# low_power_rfnode.net
KiCad netlist of a schematic drawn in EAGLE
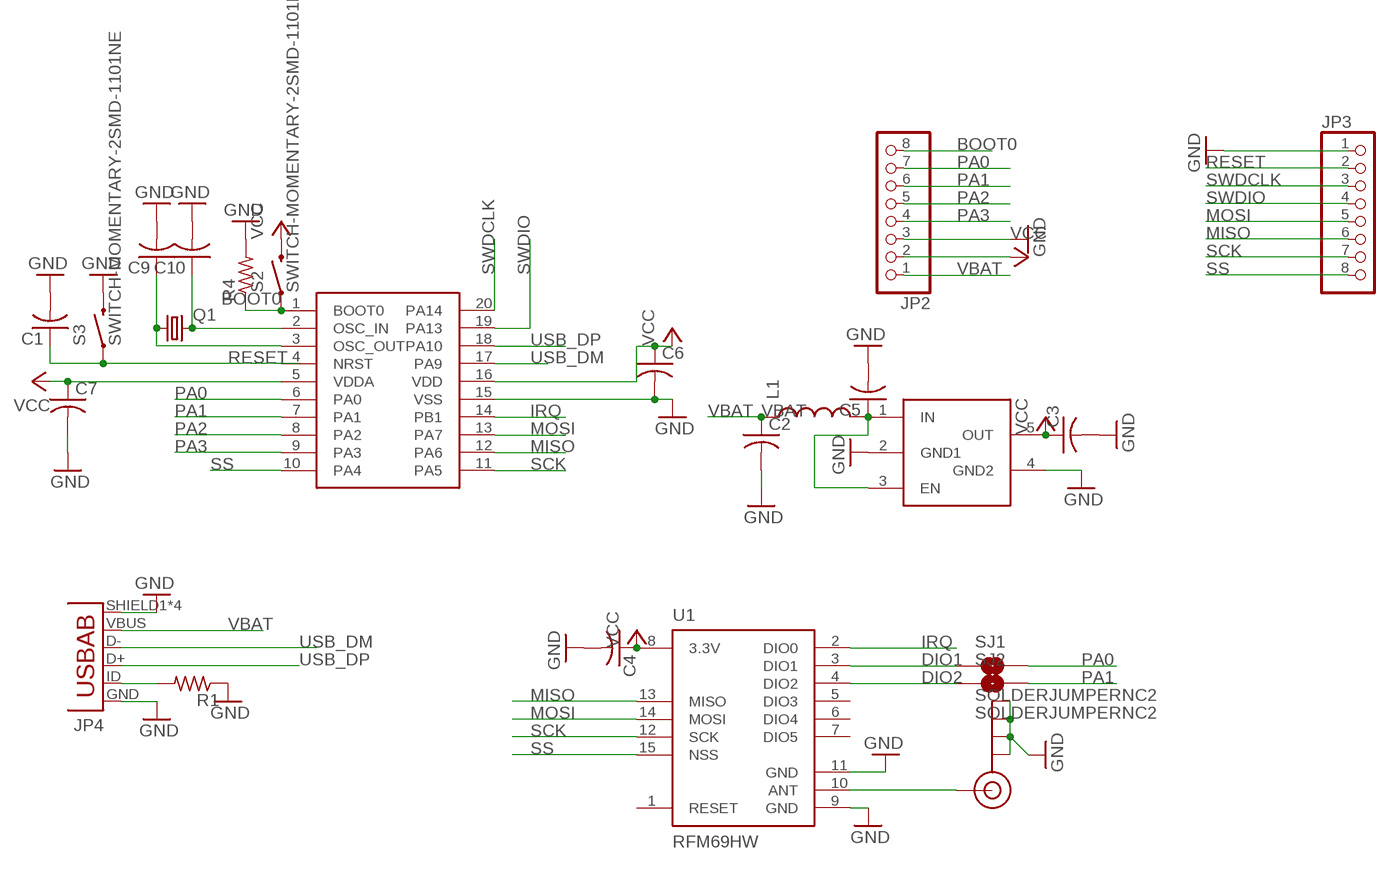
[diagram p0: schematic, sheet 1]

(export (version "E")
  (design (tool "Eeschema 10.0.6"))
  (components
    (comp (ref "C1")
      (value "C-USC0805K")
      (footprint "eagle-import:C0805K")
      (libsource (lib "eagle-import") (part "C-USC0805K"))
    )
    (comp (ref "C2")
      (value "C-USC0805K")
      (footprint "eagle-import:C0805K")
      (libsource (lib "eagle-import") (part "C-USC0805K"))
    )
    (comp (ref "C3")
      (value "C-USC0805K")
      (footprint "eagle-import:C0805K")
      (libsource (lib "eagle-import") (part "C-USC0805K"))
    )
    (comp (ref "C4")
      (value "C-USC0805K")
      (footprint "eagle-import:C0805K")
      (libsource (lib "eagle-import") (part "C-USC0805K"))
    )
    (comp (ref "C5")
      (value "C-USC0805K")
      (footprint "eagle-import:C0805K")
      (libsource (lib "eagle-import") (part "C-USC0805K"))
    )
    (comp (ref "C6")
      (value "C-USC0805K")
      (footprint "eagle-import:C0805K")
      (libsource (lib "eagle-import") (part "C-USC0805K"))
    )
    (comp (ref "C7")
      (value "C-USC0805K")
      (footprint "eagle-import:C0805K")
      (libsource (lib "eagle-import") (part "C-USC0805K"))
    )
    (comp (ref "C9")
      (value "C-USC0805K")
      (footprint "eagle-import:C0805K")
      (libsource (lib "eagle-import") (part "C-USC0805K"))
    )
    (comp (ref "C10")
      (value "C-USC0805K")
      (footprint "eagle-import:C0805K")
      (libsource (lib "eagle-import") (part "C-USC0805K"))
    )
    (comp (ref "J1")
      (value "SMA_EDGE")
      (footprint "eagle-import:SMA-EDGE")
      (libsource (lib "eagle-import") (part "SMA_EDGE"))
    )
    (comp (ref "JP2")
      (value "PINHD-1X8BIG")
      (footprint "eagle-import:1X08-BIG")
      (libsource (lib "eagle-import") (part "PINHD-1X8BIG"))
    )
    (comp (ref "JP3")
      (value "PINHD-1X8BIG")
      (footprint "eagle-import:1X08-BIG")
      (libsource (lib "eagle-import") (part "PINHD-1X8BIG"))
    )
    (comp (ref "JP4")
      (value "USB-AB")
      (footprint "eagle-import:USB-AB-MICRO-SMD")
      (libsource (lib "eagle-import") (part "USB-AB"))
    )
    (comp (ref "L1")
      (value "INDUCTOR0805")
      (footprint "eagle-import:0805")
      (libsource (lib "eagle-import") (part "INDUCTOR0805"))
    )
    (comp (ref "Q1")
      (value "CRYSTALHC49S")
      (footprint "eagle-import:HC49_S")
      (libsource (lib "eagle-import") (part "CRYSTALHC49S"))
    )
    (comp (ref "R1")
      (value "R-US_R0805")
      (footprint "eagle-import:R0805")
      (libsource (lib "eagle-import") (part "R-US_R0805"))
    )
    (comp (ref "R4")
      (value "R-US_R0805")
      (footprint "eagle-import:R0805")
      (libsource (lib "eagle-import") (part "R-US_R0805"))
    )
    (comp (ref "REG")
      (value "TPS783")
      (footprint "eagle-import:SOT23-5")
      (libsource (lib "eagle-import") (part "TPS783"))
    )
    (comp (ref "S2")
      (value "SWITCH-MOMENTARY-2SMD-1101NE")
      (footprint "eagle-import:TACTILE-SWITCH-1101NE")
      (libsource (lib "eagle-import") (part "SWITCH-MOMENTARY-2SMD-1101NE"))
    )
    (comp (ref "S3")
      (value "SWITCH-MOMENTARY-2SMD-1101NE")
      (footprint "eagle-import:TACTILE-SWITCH-1101NE")
      (libsource (lib "eagle-import") (part "SWITCH-MOMENTARY-2SMD-1101NE"))
    )
    (comp (ref "SJ1")
      (value "SOLDERJUMPERNC2")
      (footprint "eagle-import:SJ_2S-NOTRACE")
      (libsource (lib "eagle-import") (part "SOLDERJUMPERNC2"))
    )
    (comp (ref "SJ2")
      (value "SOLDERJUMPERNC2")
      (footprint "eagle-import:SJ_2S-NOTRACE")
      (libsource (lib "eagle-import") (part "SOLDERJUMPERNC2"))
    )
    (comp (ref "U$1")
      (value "STM32F0")
      (footprint "eagle-import:TSSOP20")
      (libsource (lib "eagle-import") (part "STM32F0"))
    )
    (comp (ref "U1")
      (value "RFM69HW")
      (footprint "eagle-import:RFM69W-XXXS2")
      (libsource (lib "eagle-import") (part "RFM69HW"))
    )
  )
  (nets
    (net (code "1") (name "/BOOT0") (class "Default")
      (node (ref "JP2") (pin "8") (pinfunction "8_8") (pintype "passive"))
      (node (ref "R4") (pin "1") (pinfunction "1_1") (pintype "passive"))
      (node (ref "S2") (pin "1") (pinfunction "1_1") (pintype "passive"))
      (node (ref "U$1") (pin "1") (pinfunction "BOOT0_1") (pintype "bidirectional"))
    )
    (net (code "2") (name "/DIO1") (class "Default")
      (node (ref "SJ1") (pin "1") (pinfunction "1_1") (pintype "passive"))
      (node (ref "U1") (pin "3") (pinfunction "DIO1_3") (pintype "bidirectional"))
    )
    (net (code "3") (name "/DIO2") (class "Default")
      (node (ref "SJ2") (pin "1") (pinfunction "1_1") (pintype "passive"))
      (node (ref "U1") (pin "4") (pinfunction "DIO2_4") (pintype "bidirectional"))
    )
    (net (code "4") (name "/IRQ") (class "Default")
      (node (ref "U$1") (pin "14") (pinfunction "PB1_14") (pintype "bidirectional"))
      (node (ref "U1") (pin "2") (pinfunction "DIO0_2") (pintype "bidirectional"))
    )
    (net (code "5") (name "/MISO") (class "Default")
      (node (ref "JP3") (pin "6") (pinfunction "6_6") (pintype "passive"))
      (node (ref "U$1") (pin "12") (pinfunction "PA6_12") (pintype "bidirectional"))
      (node (ref "U1") (pin "13") (pinfunction "MISO_13") (pintype "bidirectional"))
    )
    (net (code "6") (name "/MOSI") (class "Default")
      (node (ref "JP3") (pin "5") (pinfunction "5_5") (pintype "passive"))
      (node (ref "U$1") (pin "13") (pinfunction "PA7_13") (pintype "bidirectional"))
      (node (ref "U1") (pin "14") (pinfunction "MOSI_14") (pintype "input"))
    )
    (net (code "7") (name "/PA0") (class "Default")
      (node (ref "JP2") (pin "7") (pinfunction "7_7") (pintype "passive"))
      (node (ref "SJ1") (pin "2") (pinfunction "2_2") (pintype "passive"))
      (node (ref "U$1") (pin "6") (pinfunction "PA0_6") (pintype "bidirectional"))
    )
    (net (code "8") (name "/PA1") (class "Default")
      (node (ref "JP2") (pin "6") (pinfunction "6_6") (pintype "passive"))
      (node (ref "SJ2") (pin "2") (pinfunction "2_2") (pintype "passive"))
      (node (ref "U$1") (pin "7") (pinfunction "PA1_7") (pintype "bidirectional"))
    )
    (net (code "9") (name "/PA2") (class "Default")
      (node (ref "JP2") (pin "5") (pinfunction "5_5") (pintype "passive"))
      (node (ref "U$1") (pin "8") (pinfunction "PA2_8") (pintype "bidirectional"))
    )
    (net (code "10") (name "/PA3") (class "Default")
      (node (ref "JP2") (pin "4") (pinfunction "4_4") (pintype "passive"))
      (node (ref "U$1") (pin "9") (pinfunction "PA3_9") (pintype "bidirectional"))
    )
    (net (code "11") (name "/RESET") (class "Default")
      (node (ref "C1") (pin "1") (pinfunction "1_1") (pintype "passive"))
      (node (ref "JP3") (pin "2") (pinfunction "2_2") (pintype "passive"))
      (node (ref "S3") (pin "1") (pinfunction "1_1") (pintype "passive"))
      (node (ref "U$1") (pin "4") (pinfunction "NRST_4") (pintype "bidirectional"))
    )
    (net (code "12") (name "/SCK") (class "Default")
      (node (ref "JP3") (pin "7") (pinfunction "7_7") (pintype "passive"))
      (node (ref "U$1") (pin "11") (pinfunction "PA5_11") (pintype "bidirectional"))
      (node (ref "U1") (pin "12") (pinfunction "SCK_12") (pintype "input"))
    )
    (net (code "13") (name "/SS") (class "Default")
      (node (ref "JP3") (pin "8") (pinfunction "8_8") (pintype "passive"))
      (node (ref "U$1") (pin "10") (pinfunction "PA4_10") (pintype "bidirectional"))
      (node (ref "U1") (pin "15") (pinfunction "NSS_15") (pintype "input"))
    )
    (net (code "14") (name "/SWDCLK") (class "Default")
      (node (ref "JP3") (pin "3") (pinfunction "3_3") (pintype "passive"))
      (node (ref "U$1") (pin "20") (pinfunction "PA14_20") (pintype "bidirectional"))
    )
    (net (code "15") (name "/SWDIO") (class "Default")
      (node (ref "JP3") (pin "4") (pinfunction "4_4") (pintype "passive"))
      (node (ref "U$1") (pin "19") (pinfunction "PA13_19") (pintype "bidirectional"))
    )
    (net (code "16") (name "/USB_DM") (class "Default")
      (node (ref "JP4") (pin "D-") (pinfunction "D-_D-") (pintype "bidirectional"))
      (node (ref "U$1") (pin "17") (pinfunction "PA9_17") (pintype "bidirectional"))
    )
    (net (code "17") (name "/USB_DP") (class "Default")
      (node (ref "JP4") (pin "D+") (pinfunction "D+_D+") (pintype "bidirectional"))
      (node (ref "U$1") (pin "18") (pinfunction "PA10_18") (pintype "bidirectional"))
    )
    (net (code "18") (name "/VBAT") (class "Default")
      (node (ref "C2") (pin "1") (pinfunction "1_1") (pintype "passive"))
      (node (ref "JP2") (pin "1") (pinfunction "1_1") (pintype "passive"))
      (node (ref "JP4") (pin "VBUS") (pinfunction "VBUS_VBUS") (pintype "bidirectional"))
      (node (ref "L1") (pin "1") (pinfunction "1_1") (pintype "passive"))
    )
    (net (code "19") (name "GND") (class "Default")
      (node (ref "C1") (pin "2") (pinfunction "2_2") (pintype "passive"))
      (node (ref "C10") (pin "2") (pinfunction "2_2") (pintype "passive"))
      (node (ref "C2") (pin "2") (pinfunction "2_2") (pintype "passive"))
      (node (ref "C3") (pin "2") (pinfunction "2_2") (pintype "passive"))
      (node (ref "C4") (pin "2") (pinfunction "2_2") (pintype "passive"))
      (node (ref "C5") (pin "2") (pinfunction "2_2") (pintype "passive"))
      (node (ref "C6") (pin "2") (pinfunction "2_2") (pintype "passive"))
      (node (ref "C7") (pin "2") (pinfunction "2_2") (pintype "passive"))
      (node (ref "C9") (pin "2") (pinfunction "2_2") (pintype "passive"))
      (node (ref "J1") (pin "GND@0") (pinfunction "GND_GND@0") (pintype "bidirectional"))
      (node (ref "J1") (pin "GND@1") (pinfunction "GND_GND@1") (pintype "bidirectional"))
      (node (ref "J1") (pin "GND@2") (pinfunction "GND_GND@2") (pintype "bidirectional"))
      (node (ref "J1") (pin "GND@3") (pinfunction "GND_GND@3") (pintype "bidirectional"))
      (node (ref "JP2") (pin "3") (pinfunction "3_3") (pintype "passive"))
      (node (ref "JP3") (pin "1") (pinfunction "1_1") (pintype "passive"))
      (node (ref "JP4") (pin "GND") (pinfunction "GND_GND") (pintype "bidirectional"))
      (node (ref "JP4") (pin "SHIELD1") (pinfunction "SHIELD_SHIELD1") (pintype "bidirectional"))
      (node (ref "JP4") (pin "SHIELD2") (pinfunction "SHIELD_SHIELD2") (pintype "bidirectional"))
      (node (ref "JP4") (pin "SHIELD3") (pinfunction "SHIELD_SHIELD3") (pintype "bidirectional"))
      (node (ref "JP4") (pin "SHIELD4") (pinfunction "SHIELD_SHIELD4") (pintype "bidirectional"))
      (node (ref "R1") (pin "1") (pinfunction "1_1") (pintype "passive"))
      (node (ref "R4") (pin "2") (pinfunction "2_2") (pintype "passive"))
      (node (ref "REG") (pin "2") (pinfunction "GND1_2") (pintype "power_in"))
      (node (ref "REG") (pin "4") (pinfunction "GND2_4") (pintype "power_in"))
      (node (ref "S3") (pin "2") (pinfunction "2_2") (pintype "passive"))
      (node (ref "U$1") (pin "15") (pinfunction "VSS_15") (pintype "bidirectional"))
      (node (ref "U1") (pin "11") (pinfunction "GND_11") (pintype "power_in"))
      (node (ref "U1") (pin "9") (pinfunction "GND_9") (pintype "power_in"))
    )
    (net (code "20") (name "Net-(J1-SIGNAL)") (class "Default")
      (node (ref "J1") (pin "SIG") (pinfunction "SIGNAL_SIG") (pintype "bidirectional"))
      (node (ref "U1") (pin "10") (pinfunction "ANT_10") (pintype "passive"))
    )
    (net (code "21") (name "Net-(JP4-USBID)") (class "Default")
      (node (ref "JP4") (pin "ID") (pinfunction "USBID_ID") (pintype "bidirectional"))
      (node (ref "R1") (pin "2") (pinfunction "2_2") (pintype "passive"))
    )
    (net (code "22") (name "Net-(REG-EN)") (class "Default")
      (node (ref "C5") (pin "1") (pinfunction "1_1") (pintype "passive"))
      (node (ref "L1") (pin "2") (pinfunction "2_2") (pintype "passive"))
      (node (ref "REG") (pin "1") (pinfunction "IN_1") (pintype "power_in"))
      (node (ref "REG") (pin "3") (pinfunction "EN_3") (pintype "bidirectional"))
    )
    (net (code "23") (name "Net-(U$1-OSC_IN)") (class "Default")
      (node (ref "C10") (pin "1") (pinfunction "1_1") (pintype "passive"))
      (node (ref "Q1") (pin "2") (pinfunction "2_2") (pintype "passive"))
      (node (ref "U$1") (pin "2") (pinfunction "OSC_IN_2") (pintype "bidirectional"))
    )
    (net (code "24") (name "Net-(U$1-OSC_OUT)") (class "Default")
      (node (ref "C9") (pin "1") (pinfunction "1_1") (pintype "passive"))
      (node (ref "Q1") (pin "1") (pinfunction "1_1") (pintype "passive"))
      (node (ref "U$1") (pin "3") (pinfunction "OSC_OUT_3") (pintype "bidirectional"))
    )
    (net (code "25") (name "VCC") (class "Default")
      (node (ref "C3") (pin "1") (pinfunction "1_1") (pintype "passive"))
      (node (ref "C4") (pin "1") (pinfunction "1_1") (pintype "passive"))
      (node (ref "C6") (pin "1") (pinfunction "1_1") (pintype "passive"))
      (node (ref "C7") (pin "1") (pinfunction "1_1") (pintype "passive"))
      (node (ref "JP2") (pin "2") (pinfunction "2_2") (pintype "passive"))
      (node (ref "REG") (pin "5") (pinfunction "OUT_5") (pintype "power_in"))
      (node (ref "S2") (pin "2") (pinfunction "2_2") (pintype "passive"))
      (node (ref "U$1") (pin "16") (pinfunction "VDD_16") (pintype "bidirectional"))
      (node (ref "U$1") (pin "5") (pinfunction "VDDA_5") (pintype "bidirectional"))
      (node (ref "U1") (pin "8") (pinfunction "3.3V_8") (pintype "power_in"))
    )
    (net (code "26") (name "unconnected-(U1-DIO3-Pad5)") (class "Default")
      (node (ref "U1") (pin "5") (pinfunction "DIO3_5") (pintype "bidirectional"))
    )
    (net (code "27") (name "unconnected-(U1-DIO4-Pad6)") (class "Default")
      (node (ref "U1") (pin "6") (pinfunction "DIO4_6") (pintype "bidirectional"))
    )
    (net (code "28") (name "unconnected-(U1-DIO5-Pad7)") (class "Default")
      (node (ref "U1") (pin "7") (pinfunction "DIO5_7") (pintype "bidirectional"))
    )
    (net (code "29") (name "unconnected-(U1-RESET-Pad1)") (class "Default")
      (node (ref "U1") (pin "1") (pinfunction "RESET_1") (pintype "input"))
    )
  )
)
